# flight_computer.net
KiCad netlist of a schematic drawn in EAGLE
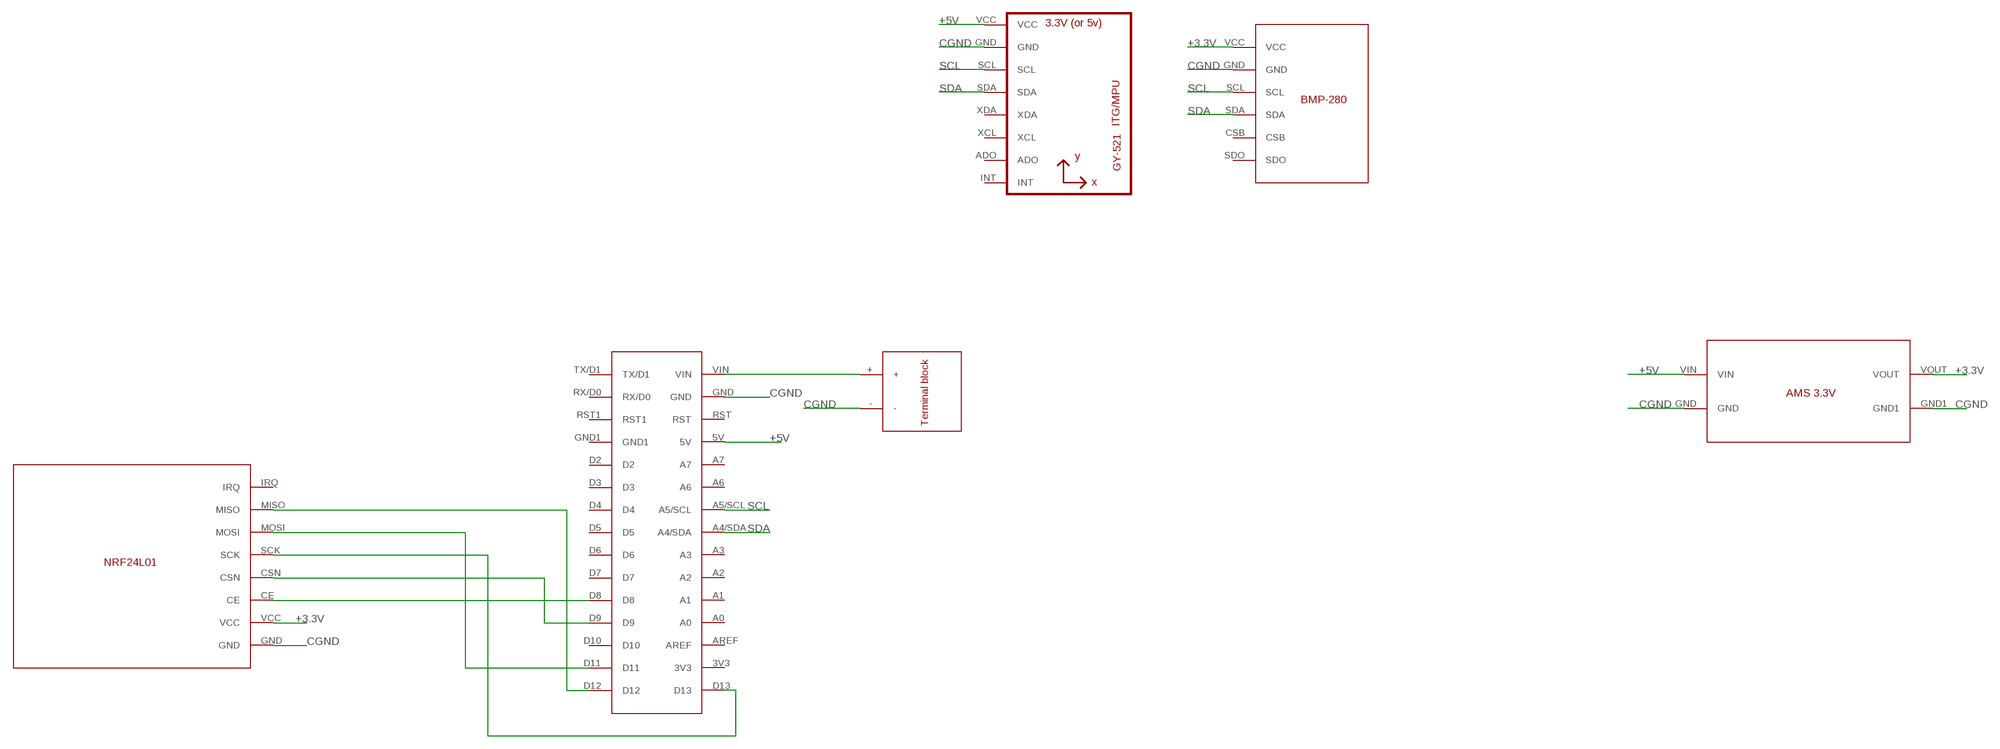
[diagram p0: schematic, sheet 1]

(export (version "E")
  (design (tool "Eeschema 10.0.6"))
  (components
    (comp (ref "U$1")
      (value "ARDUINONANO")
      (footprint "eagle-import:ARDUINONANO")
      (libsource (lib "eagle-import") (part "ARDUINONANO"))
    )
    (comp (ref "U$2")
      (value "3.3V_REGULATOR")
      (footprint "eagle-import:3.3V_REGULATOR")
      (libsource (lib "eagle-import") (part "3.3V_REGULATOR"))
    )
    (comp (ref "U$3")
      (value "NRF24L01")
      (footprint "eagle-import:NRF24L01")
      (libsource (lib "eagle-import") (part "NRF24L01"))
    )
    (comp (ref "U$4")
      (value "BMP280")
      (footprint "eagle-import:BMP280")
      (libsource (lib "eagle-import") (part "BMP280"))
    )
    (comp (ref "U$5")
      (value "TERMINAL_BLOCK")
      (footprint "eagle-import:TERMINAL_BLOCK")
      (libsource (lib "eagle-import") (part "TERMINAL_BLOCK"))
    )
    (comp (ref "U1")
      (value "GY-521MPU6050")
      (footprint "eagle-import:GY-521")
      (libsource (lib "eagle-import") (part "GY-521MPU6050"))
    )
  )
  (nets
    (net (code "1") (name "/+3.3V") (class "Default")
      (node (ref "U$2") (pin "VOUT") (pinfunction "VOUT_VOUT") (pintype "bidirectional"))
      (node (ref "U$3") (pin "VCC") (pinfunction "VCC_VCC") (pintype "bidirectional"))
      (node (ref "U$4") (pin "VCC") (pinfunction "VCC_VCC") (pintype "bidirectional"))
    )
    (net (code "2") (name "/+5V") (class "Default")
      (node (ref "U$1") (pin "5V") (pinfunction "5V_5V") (pintype "bidirectional"))
      (node (ref "U$2") (pin "VIN") (pinfunction "VIN_VIN") (pintype "bidirectional"))
      (node (ref "U1") (pin "VCC") (pinfunction "VCC_VCC") (pintype "bidirectional"))
    )
    (net (code "3") (name "/CGND") (class "Default")
      (node (ref "U$1") (pin "GND") (pinfunction "GND_GND") (pintype "bidirectional"))
      (node (ref "U$2") (pin "GND") (pinfunction "GND_GND") (pintype "bidirectional"))
      (node (ref "U$2") (pin "GND1") (pinfunction "GND1_GND1") (pintype "bidirectional"))
      (node (ref "U$3") (pin "GND") (pinfunction "GND_GND") (pintype "bidirectional"))
      (node (ref "U$4") (pin "GND") (pinfunction "GND_GND") (pintype "bidirectional"))
      (node (ref "U$5") (pin "-") (pinfunction "-_-") (pintype "bidirectional"))
      (node (ref "U1") (pin "GND") (pinfunction "GND_GND") (pintype "bidirectional"))
    )
    (net (code "4") (name "/SCL") (class "Default")
      (node (ref "U$1") (pin "A5/SCL") (pinfunction "A5/SCL_A5/SCL") (pintype "bidirectional"))
      (node (ref "U$4") (pin "SCL") (pinfunction "SCL_SCL") (pintype "bidirectional"))
      (node (ref "U1") (pin "SCL") (pinfunction "SCL_SCL") (pintype "bidirectional"))
    )
    (net (code "5") (name "/SDA") (class "Default")
      (node (ref "U$1") (pin "A4/SDA") (pinfunction "A4/SDA_A4/SDA") (pintype "bidirectional"))
      (node (ref "U$4") (pin "SDA") (pinfunction "SDA_SDA") (pintype "bidirectional"))
      (node (ref "U1") (pin "SDA") (pinfunction "SDA_SDA") (pintype "bidirectional"))
    )
    (net (code "6") (name "Net-(U$1-PadD8)") (class "Default")
      (node (ref "U$1") (pin "D8") (pinfunction "D8_D8") (pintype "bidirectional"))
      (node (ref "U$3") (pin "CE") (pinfunction "CE_CE") (pintype "bidirectional"))
    )
    (net (code "7") (name "Net-(U$1-PadD9)") (class "Default")
      (node (ref "U$1") (pin "D9") (pinfunction "D9_D9") (pintype "bidirectional"))
      (node (ref "U$3") (pin "CSN") (pinfunction "CSN_CSN") (pintype "bidirectional"))
    )
    (net (code "8") (name "Net-(U$1-PadD11)") (class "Default")
      (node (ref "U$1") (pin "D11") (pinfunction "D11_D11") (pintype "bidirectional"))
      (node (ref "U$3") (pin "MOSI") (pinfunction "MOSI_MOSI") (pintype "bidirectional"))
    )
    (net (code "9") (name "Net-(U$1-PadD12)") (class "Default")
      (node (ref "U$1") (pin "D12") (pinfunction "D12_D12") (pintype "bidirectional"))
      (node (ref "U$3") (pin "MISO") (pinfunction "MISO_MISO") (pintype "bidirectional"))
    )
    (net (code "10") (name "Net-(U$1-PadD13)") (class "Default")
      (node (ref "U$1") (pin "D13") (pinfunction "D13_D13") (pintype "bidirectional"))
      (node (ref "U$3") (pin "SCK") (pinfunction "SCK_SCK") (pintype "bidirectional"))
    )
    (net (code "11") (name "Net-(U$1-PadVIN)") (class "Default")
      (node (ref "U$1") (pin "VIN") (pinfunction "VIN_VIN") (pintype "bidirectional"))
      (node (ref "U$5") (pin "+") (pinfunction "+_+") (pintype "bidirectional"))
    )
    (net (code "12") (name "unconnected-(U$1-Pad3V3)") (class "Default")
      (node (ref "U$1") (pin "3V3") (pinfunction "3V3_3V3") (pintype "bidirectional"))
    )
    (net (code "13") (name "unconnected-(U$1-PadA0)") (class "Default")
      (node (ref "U$1") (pin "A0") (pinfunction "A0_A0") (pintype "bidirectional"))
    )
    (net (code "14") (name "unconnected-(U$1-PadA1)") (class "Default")
      (node (ref "U$1") (pin "A1") (pinfunction "A1_A1") (pintype "bidirectional"))
    )
    (net (code "15") (name "unconnected-(U$1-PadA2)") (class "Default")
      (node (ref "U$1") (pin "A2") (pinfunction "A2_A2") (pintype "bidirectional"))
    )
    (net (code "16") (name "unconnected-(U$1-PadA3)") (class "Default")
      (node (ref "U$1") (pin "A3") (pinfunction "A3_A3") (pintype "bidirectional"))
    )
    (net (code "17") (name "unconnected-(U$1-PadA6)") (class "Default")
      (node (ref "U$1") (pin "A6") (pinfunction "A6_A6") (pintype "bidirectional"))
    )
    (net (code "18") (name "unconnected-(U$1-PadA7)") (class "Default")
      (node (ref "U$1") (pin "A7") (pinfunction "A7_A7") (pintype "bidirectional"))
    )
    (net (code "19") (name "unconnected-(U$1-PadAREF)") (class "Default")
      (node (ref "U$1") (pin "AREF") (pinfunction "AREF_AREF") (pintype "bidirectional"))
    )
    (net (code "20") (name "unconnected-(U$1-PadD2)") (class "Default")
      (node (ref "U$1") (pin "D2") (pinfunction "D2_D2") (pintype "bidirectional"))
    )
    (net (code "21") (name "unconnected-(U$1-PadD3)") (class "Default")
      (node (ref "U$1") (pin "D3") (pinfunction "D3_D3") (pintype "bidirectional"))
    )
    (net (code "22") (name "unconnected-(U$1-PadD4)") (class "Default")
      (node (ref "U$1") (pin "D4") (pinfunction "D4_D4") (pintype "bidirectional"))
    )
    (net (code "23") (name "unconnected-(U$1-PadD5)") (class "Default")
      (node (ref "U$1") (pin "D5") (pinfunction "D5_D5") (pintype "bidirectional"))
    )
    (net (code "24") (name "unconnected-(U$1-PadD6)") (class "Default")
      (node (ref "U$1") (pin "D6") (pinfunction "D6_D6") (pintype "bidirectional"))
    )
    (net (code "25") (name "unconnected-(U$1-PadD7)") (class "Default")
      (node (ref "U$1") (pin "D7") (pinfunction "D7_D7") (pintype "bidirectional"))
    )
    (net (code "26") (name "unconnected-(U$1-PadD10)") (class "Default")
      (node (ref "U$1") (pin "D10") (pinfunction "D10_D10") (pintype "bidirectional"))
    )
    (net (code "27") (name "unconnected-(U$1-PadGND1)") (class "Default")
      (node (ref "U$1") (pin "GND1") (pinfunction "GND1_GND1") (pintype "bidirectional"))
    )
    (net (code "28") (name "unconnected-(U$1-PadRST)") (class "Default")
      (node (ref "U$1") (pin "RST") (pinfunction "RST_RST") (pintype "bidirectional"))
    )
    (net (code "29") (name "unconnected-(U$1-PadRST1)") (class "Default")
      (node (ref "U$1") (pin "RST1") (pinfunction "RST1_RST1") (pintype "bidirectional"))
    )
    (net (code "30") (name "unconnected-(U$1-PadRX{slash}D0)") (class "Default")
      (node (ref "U$1") (pin "RX/D0") (pinfunction "RX/D0_RX/D0") (pintype "bidirectional"))
    )
    (net (code "31") (name "unconnected-(U$1-PadTX{slash}D1)") (class "Default")
      (node (ref "U$1") (pin "TX/D1") (pinfunction "TX/D1_TX/D1") (pintype "bidirectional"))
    )
    (net (code "32") (name "unconnected-(U$3-PadIRQ)") (class "Default")
      (node (ref "U$3") (pin "IRQ") (pinfunction "IRQ_IRQ") (pintype "bidirectional"))
    )
    (net (code "33") (name "unconnected-(U$4-PadCSB)") (class "Default")
      (node (ref "U$4") (pin "CSB") (pinfunction "CSB_CSB") (pintype "bidirectional"))
    )
    (net (code "34") (name "unconnected-(U$4-PadSDO)") (class "Default")
      (node (ref "U$4") (pin "SDO") (pinfunction "SDO_SDO") (pintype "bidirectional"))
    )
    (net (code "35") (name "unconnected-(U1-PadADO)") (class "Default")
      (node (ref "U1") (pin "ADO") (pinfunction "ADO_ADO") (pintype "bidirectional"))
    )
    (net (code "36") (name "unconnected-(U1-PadINT)") (class "Default")
      (node (ref "U1") (pin "INT") (pinfunction "INT_INT") (pintype "bidirectional"))
    )
    (net (code "37") (name "unconnected-(U1-PadXCL)") (class "Default")
      (node (ref "U1") (pin "XCL") (pinfunction "XCL_XCL") (pintype "bidirectional"))
    )
    (net (code "38") (name "unconnected-(U1-PadXDA)") (class "Default")
      (node (ref "U1") (pin "XDA") (pinfunction "XDA_XDA") (pintype "bidirectional"))
    )
  )
)
